# Power-up_delay.net
KiCad netlist of a schematic drawn in Altium Designer
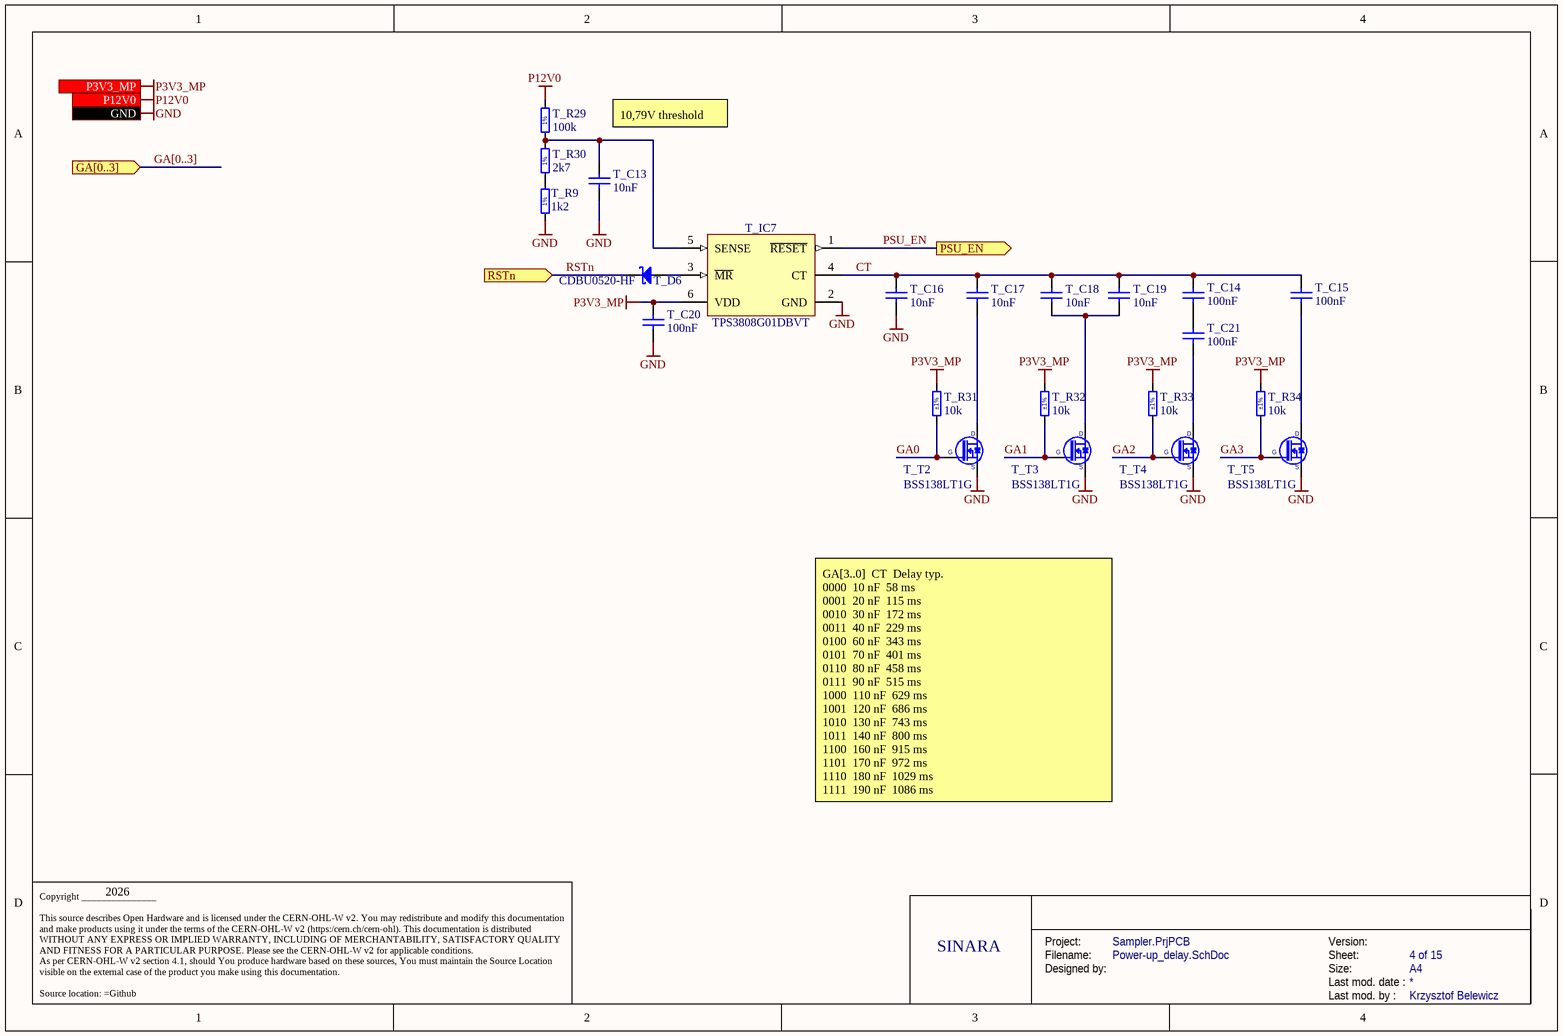
[diagram p0: Power-up_delay.SchDoc]

(export (version "E")
  (design (tool "Eeschema 10.0.6"))
  (components
    (comp (ref "T_C13")
      (value "10nF")
      (footprint "CAPC1005X55N")
      (description "Non-polarised capacitor")
      (fields
        (field (name "PART NUMBER") "CC0402_10NF_50V_5%_X7R")
        (field (name "VOLTAGE") "50V")
        (field (name "AUTHOR") "CERN DEM BC")
      )
      (libsource (lib "Capacitors") (part "Capacitor - non polarized"))
    )
    (comp (ref "T_C14")
      (value "100nF")
      (footprint "CAPC1005X55N")
      (description "Non-polarised capacitor")
      (fields
        (field (name "PART NUMBER") "CC0402_100NF_50V_10%_X7R")
        (field (name "VOLTAGE") "50V")
        (field (name "AUTHOR") "CERN DEM MR")
      )
      (libsource (lib "Capacitors") (part "Capacitor - non polarized"))
    )
    (comp (ref "T_C15")
      (value "100nF")
      (footprint "CAPC1005X55N")
      (description "Non-polarised capacitor")
      (fields
        (field (name "PART NUMBER") "CC0402_100NF_50V_10%_X7R")
        (field (name "VOLTAGE") "50V")
        (field (name "AUTHOR") "CERN DEM MR")
      )
      (libsource (lib "Capacitors") (part "Capacitor - non polarized"))
    )
    (comp (ref "T_C16")
      (value "10nF")
      (footprint "CAPC1005X55N")
      (description "Non-polarised capacitor")
      (fields
        (field (name "PART NUMBER") "CC0402_10NF_50V_5%_X7R")
        (field (name "VOLTAGE") "50V")
        (field (name "AUTHOR") "CERN DEM BC")
      )
      (libsource (lib "Capacitors") (part "Capacitor - non polarized"))
    )
    (comp (ref "T_C17")
      (value "10nF")
      (footprint "CAPC1005X55N")
      (description "Non-polarised capacitor")
      (fields
        (field (name "PART NUMBER") "CC0402_10NF_50V_5%_X7R")
        (field (name "VOLTAGE") "50V")
        (field (name "AUTHOR") "CERN DEM BC")
      )
      (libsource (lib "Capacitors") (part "Capacitor - non polarized"))
    )
    (comp (ref "T_C18")
      (value "10nF")
      (footprint "CAPC1005X55N")
      (description "Non-polarised capacitor")
      (fields
        (field (name "PART NUMBER") "CC0402_10NF_50V_5%_X7R")
        (field (name "VOLTAGE") "50V")
        (field (name "AUTHOR") "CERN DEM BC")
      )
      (libsource (lib "Capacitors") (part "Capacitor - non polarized"))
    )
    (comp (ref "T_C19")
      (value "10nF")
      (footprint "CAPC1005X55N")
      (description "Non-polarised capacitor")
      (fields
        (field (name "PART NUMBER") "CC0402_10NF_50V_5%_X7R")
        (field (name "VOLTAGE") "50V")
        (field (name "AUTHOR") "CERN DEM BC")
      )
      (libsource (lib "Capacitors") (part "Capacitor - non polarized"))
    )
    (comp (ref "T_C20")
      (value "100nF")
      (footprint "CAPC1005X55N")
      (description "Non-polarised capacitor")
      (fields
        (field (name "PART NUMBER") "CC0402_100NF_50V_10%_X7R")
        (field (name "VOLTAGE") "50V")
        (field (name "AUTHOR") "CERN DEM MR")
      )
      (libsource (lib "Capacitors") (part "Capacitor - non polarized"))
    )
    (comp (ref "T_C21")
      (value "100nF")
      (footprint "CAPC1005X55N")
      (description "Non-polarised capacitor")
      (fields
        (field (name "PART NUMBER") "CC0402_100NF_50V_10%_X7R")
        (field (name "VOLTAGE") "50V")
        (field (name "AUTHOR") "CERN DEM MR")
      )
      (libsource (lib "Capacitors") (part "Capacitor - non polarized"))
    )
    (comp (ref "T_D6")
      (value "CDBU0520-HF")
      (footprint "SOD-523F")
      (description "Schottky Diode")
      (fields
        (field (name "VOLTAGE") "20V")
        (field (name "POWER") "500mA")
        (field (name "AUTHOR") "CERN DEM HF")
      )
      (libsource (lib "ICs And Semiconductors") (part "Diode Schottky"))
    )
    (comp (ref "T_IC7")
      (value "TPS3808G01DBVT")
      (footprint "SOT95P280X145-6N")
      (description "Low Quiescent Current, Programmable-Delay Supervisory Circuit")
      (fields
        (field (name "MANUFACTURER") "TEXAS INSTRUMENTS")
        (field (name "MANUFACTURER PART NUMBER") "TPS3808G01DBV")
        (field (name "AUTHOR") "CERN DEM JLC")
      )
      (libsource (lib "ICs And Semiconductors") (part "TPS3808xxxDBV"))
    )
    (comp (ref "T_R9")
      (value "1k2")
      (footprint "RESC1608X55N")
      (description "Resistor - 1%")
      (fields
        (field (name "PART NUMBER") "R0603_1K2_1%_0.1W_100PPM")
        (field (name "POWER") "0.1W")
        (field (name "AUTHOR") "CERN DEM JLC")
      )
      (libsource (lib "Resistors") (part "Resistor - 1%"))
    )
    (comp (ref "T_R29")
      (value "100k")
      (footprint "RESC1608X55N")
      (description "Resistor - 1%")
      (fields
        (field (name "PART NUMBER") "R0603_100K_1%_0.1W_100PPM")
        (field (name "POWER") "0.1W")
        (field (name "AUTHOR") "CERN DEM JLC")
      )
      (libsource (lib "Resistors") (part "Resistor - 1%"))
    )
    (comp (ref "T_R30")
      (value "2k7")
      (footprint "RESC1608X55N")
      (description "Resistor - 1%")
      (fields
        (field (name "PART NUMBER") "R0603_2K7_1%_0.1W_100PPM")
        (field (name "POWER") "0.1W")
        (field (name "AUTHOR") "CERN DEM JLC")
      )
      (libsource (lib "Resistors") (part "Resistor - 1%"))
    )
    (comp (ref "T_R31")
      (value "10k")
      (footprint "RESC1005X40N")
      (description "Resistor - 1%")
      (fields
        (field (name "TOLERANCE") "±1%")
        (field (name "PART NUMBER") "R0402_10K_1%_0.0625W_100PPM")
        (field (name "POWER") "0.0625W")
        (field (name "AUTHOR") "CERN DEM JLC")
      )
      (libsource (lib "") (part "Resistor - 1%_1"))
    )
    (comp (ref "T_R32")
      (value "10k")
      (footprint "RESC1005X40N")
      (description "Resistor - 1%")
      (fields
        (field (name "TOLERANCE") "±1%")
        (field (name "PART NUMBER") "R0402_10K_1%_0.0625W_100PPM")
        (field (name "POWER") "0.0625W")
        (field (name "AUTHOR") "CERN DEM JLC")
      )
      (libsource (lib "") (part "Resistor - 1%_1"))
    )
    (comp (ref "T_R33")
      (value "10k")
      (footprint "RESC1005X40N")
      (description "Resistor - 1%")
      (fields
        (field (name "TOLERANCE") "±1%")
        (field (name "PART NUMBER") "R0402_10K_1%_0.0625W_100PPM")
        (field (name "POWER") "0.0625W")
        (field (name "AUTHOR") "CERN DEM JLC")
      )
      (libsource (lib "") (part "Resistor - 1%_1"))
    )
    (comp (ref "T_R34")
      (value "10k")
      (footprint "RESC1005X40N")
      (description "Resistor - 1%")
      (fields
        (field (name "TOLERANCE") "±1%")
        (field (name "PART NUMBER") "R0402_10K_1%_0.0625W_100PPM")
        (field (name "POWER") "0.0625W")
        (field (name "AUTHOR") "CERN DEM JLC")
      )
      (libsource (lib "") (part "Resistor - 1%_1"))
    )
    (comp (ref "T_T2")
      (value "BSS138LT1G")
      (footprint "SOT95P240X110-3N")
      (description "N-CHANNEL MOSFET WITH DIODE")
      (fields
        (field (name "MANUFACTURER") "ON SEMICONDUCTOR")
        (field (name "MANUFACTURER PART NUMBER") "BSS138L")
        (field (name "AUTHOR") "CERN DEM JLC")
      )
      (libsource (lib "ICs And Semiconductors") (part "N-MOSFET-D 1G 2S 3D"))
    )
    (comp (ref "T_T3")
      (value "BSS138LT1G")
      (footprint "SOT95P240X110-3N")
      (description "N-CHANNEL MOSFET WITH DIODE")
      (fields
        (field (name "MANUFACTURER") "ON SEMICONDUCTOR")
        (field (name "MANUFACTURER PART NUMBER") "BSS138L")
        (field (name "AUTHOR") "CERN DEM JLC")
      )
      (libsource (lib "ICs And Semiconductors") (part "N-MOSFET-D 1G 2S 3D"))
    )
    (comp (ref "T_T4")
      (value "BSS138LT1G")
      (footprint "SOT95P240X110-3N")
      (description "N-CHANNEL MOSFET WITH DIODE")
      (fields
        (field (name "MANUFACTURER") "ON SEMICONDUCTOR")
        (field (name "MANUFACTURER PART NUMBER") "BSS138L")
        (field (name "AUTHOR") "CERN DEM JLC")
      )
      (libsource (lib "ICs And Semiconductors") (part "N-MOSFET-D 1G 2S 3D"))
    )
    (comp (ref "T_T5")
      (value "BSS138LT1G")
      (footprint "SOT95P240X110-3N")
      (description "N-CHANNEL MOSFET WITH DIODE")
      (fields
        (field (name "MANUFACTURER") "ON SEMICONDUCTOR")
        (field (name "MANUFACTURER PART NUMBER") "BSS138L")
        (field (name "AUTHOR") "CERN DEM JLC")
      )
      (libsource (lib "ICs And Semiconductors") (part "N-MOSFET-D 1G 2S 3D"))
    )
  )
  (nets
    (net (code "1") (name "/CT") (class "Default")
      (node (ref "T_C14") (pin "2") (pinfunction "2_2") (pintype "passive"))
      (node (ref "T_C15") (pin "2") (pinfunction "2_2") (pintype "passive"))
      (node (ref "T_C16") (pin "2") (pinfunction "2_2") (pintype "passive"))
      (node (ref "T_C17") (pin "2") (pinfunction "2_2") (pintype "passive"))
      (node (ref "T_C18") (pin "2") (pinfunction "2_2") (pintype "passive"))
      (node (ref "T_C19") (pin "2") (pinfunction "2_2") (pintype "passive"))
      (node (ref "T_IC7") (pin "4") (pinfunction "CT_4") (pintype "passive"))
    )
    (net (code "2") (name "/GA0") (class "Default")
      (node (ref "T_R31") (pin "1") (pinfunction "1_1") (pintype "passive"))
      (node (ref "T_T2") (pin "1") (pinfunction "G_1") (pintype "passive"))
    )
    (net (code "3") (name "/GA1") (class "Default")
      (node (ref "T_R32") (pin "1") (pinfunction "1_1") (pintype "passive"))
      (node (ref "T_T3") (pin "1") (pinfunction "G_1") (pintype "passive"))
    )
    (net (code "4") (name "/GA2") (class "Default")
      (node (ref "T_R33") (pin "1") (pinfunction "1_1") (pintype "passive"))
      (node (ref "T_T4") (pin "1") (pinfunction "G_1") (pintype "passive"))
    )
    (net (code "5") (name "/GA3") (class "Default")
      (node (ref "T_R34") (pin "1") (pinfunction "1_1") (pintype "passive"))
      (node (ref "T_T5") (pin "1") (pinfunction "G_1") (pintype "passive"))
    )
    (net (code "7") (name "/PSU_EN") (class "Default")
      (node (ref "T_IC7") (pin "1") (pinfunction "~{RESET}_1") (pintype "output"))
    )
    (net (code "8") (name "/RSTn") (class "Default")
      (node (ref "T_D6") (pin "1") (pinfunction "C_1") (pintype "passive"))
    )
    (net (code "9") (name "GND") (class "Default")
      (node (ref "T_C13") (pin "2") (pinfunction "2_2") (pintype "passive"))
      (node (ref "T_C16") (pin "1") (pinfunction "1_1") (pintype "passive"))
      (node (ref "T_C20") (pin "1") (pinfunction "1_1") (pintype "passive"))
      (node (ref "T_IC7") (pin "2") (pinfunction "GND_2") (pintype "power_in"))
      (node (ref "T_R9") (pin "1") (pinfunction "1_1") (pintype "passive"))
      (node (ref "T_T2") (pin "2") (pinfunction "S_2") (pintype "passive"))
      (node (ref "T_T3") (pin "2") (pinfunction "S_2") (pintype "passive"))
      (node (ref "T_T4") (pin "2") (pinfunction "S_2") (pintype "passive"))
      (node (ref "T_T5") (pin "2") (pinfunction "S_2") (pintype "passive"))
    )
    (net (code "10") (name "Net-(T_C14-Pad1)") (class "Default")
      (node (ref "T_C14") (pin "1") (pinfunction "1_1") (pintype "passive"))
      (node (ref "T_C21") (pin "2") (pinfunction "2_2") (pintype "passive"))
    )
    (net (code "11") (name "Net-(T_D6-A)") (class "Default")
      (node (ref "T_D6") (pin "2") (pinfunction "A_2") (pintype "passive"))
      (node (ref "T_IC7") (pin "3") (pinfunction "~{MR}_3") (pintype "input"))
    )
    (net (code "12") (name "Net-(T_IC7-SENSE)") (class "Default")
      (node (ref "T_C13") (pin "1") (pinfunction "1_1") (pintype "passive"))
      (node (ref "T_IC7") (pin "5") (pinfunction "SENSE_5") (pintype "input"))
      (node (ref "T_R29") (pin "1") (pinfunction "1_1") (pintype "passive"))
      (node (ref "T_R30") (pin "2") (pinfunction "2_2") (pintype "passive"))
    )
    (net (code "13") (name "Net-(T_R30-Pad1)") (class "Default")
      (node (ref "T_R30") (pin "1") (pinfunction "1_1") (pintype "passive"))
      (node (ref "T_R9") (pin "2") (pinfunction "2_2") (pintype "passive"))
    )
    (net (code "14") (name "Net-(T_T2-D)") (class "Default")
      (node (ref "T_C17") (pin "1") (pinfunction "1_1") (pintype "passive"))
      (node (ref "T_T2") (pin "3") (pinfunction "D_3") (pintype "passive"))
    )
    (net (code "15") (name "Net-(T_T3-D)") (class "Default")
      (node (ref "T_C18") (pin "1") (pinfunction "1_1") (pintype "passive"))
      (node (ref "T_C19") (pin "1") (pinfunction "1_1") (pintype "passive"))
      (node (ref "T_T3") (pin "3") (pinfunction "D_3") (pintype "passive"))
    )
    (net (code "16") (name "Net-(T_T4-D)") (class "Default")
      (node (ref "T_C21") (pin "1") (pinfunction "1_1") (pintype "passive"))
      (node (ref "T_T4") (pin "3") (pinfunction "D_3") (pintype "passive"))
    )
    (net (code "17") (name "Net-(T_T5-D)") (class "Default")
      (node (ref "T_C15") (pin "1") (pinfunction "1_1") (pintype "passive"))
      (node (ref "T_T5") (pin "3") (pinfunction "D_3") (pintype "passive"))
    )
    (net (code "18") (name "P3V3_MP") (class "Default")
      (node (ref "T_C20") (pin "2") (pinfunction "2_2") (pintype "passive"))
      (node (ref "T_IC7") (pin "6") (pinfunction "VDD_6") (pintype "power_in"))
      (node (ref "T_R31") (pin "2") (pinfunction "2_2") (pintype "passive"))
      (node (ref "T_R32") (pin "2") (pinfunction "2_2") (pintype "passive"))
      (node (ref "T_R33") (pin "2") (pinfunction "2_2") (pintype "passive"))
      (node (ref "T_R34") (pin "2") (pinfunction "2_2") (pintype "passive"))
    )
    (net (code "19") (name "P12V0") (class "Default")
      (node (ref "T_R29") (pin "2") (pinfunction "2_2") (pintype "passive"))
    )
  )
)
